# OmniRotor.net
KiCad netlist of a schematic drawn in EAGLE
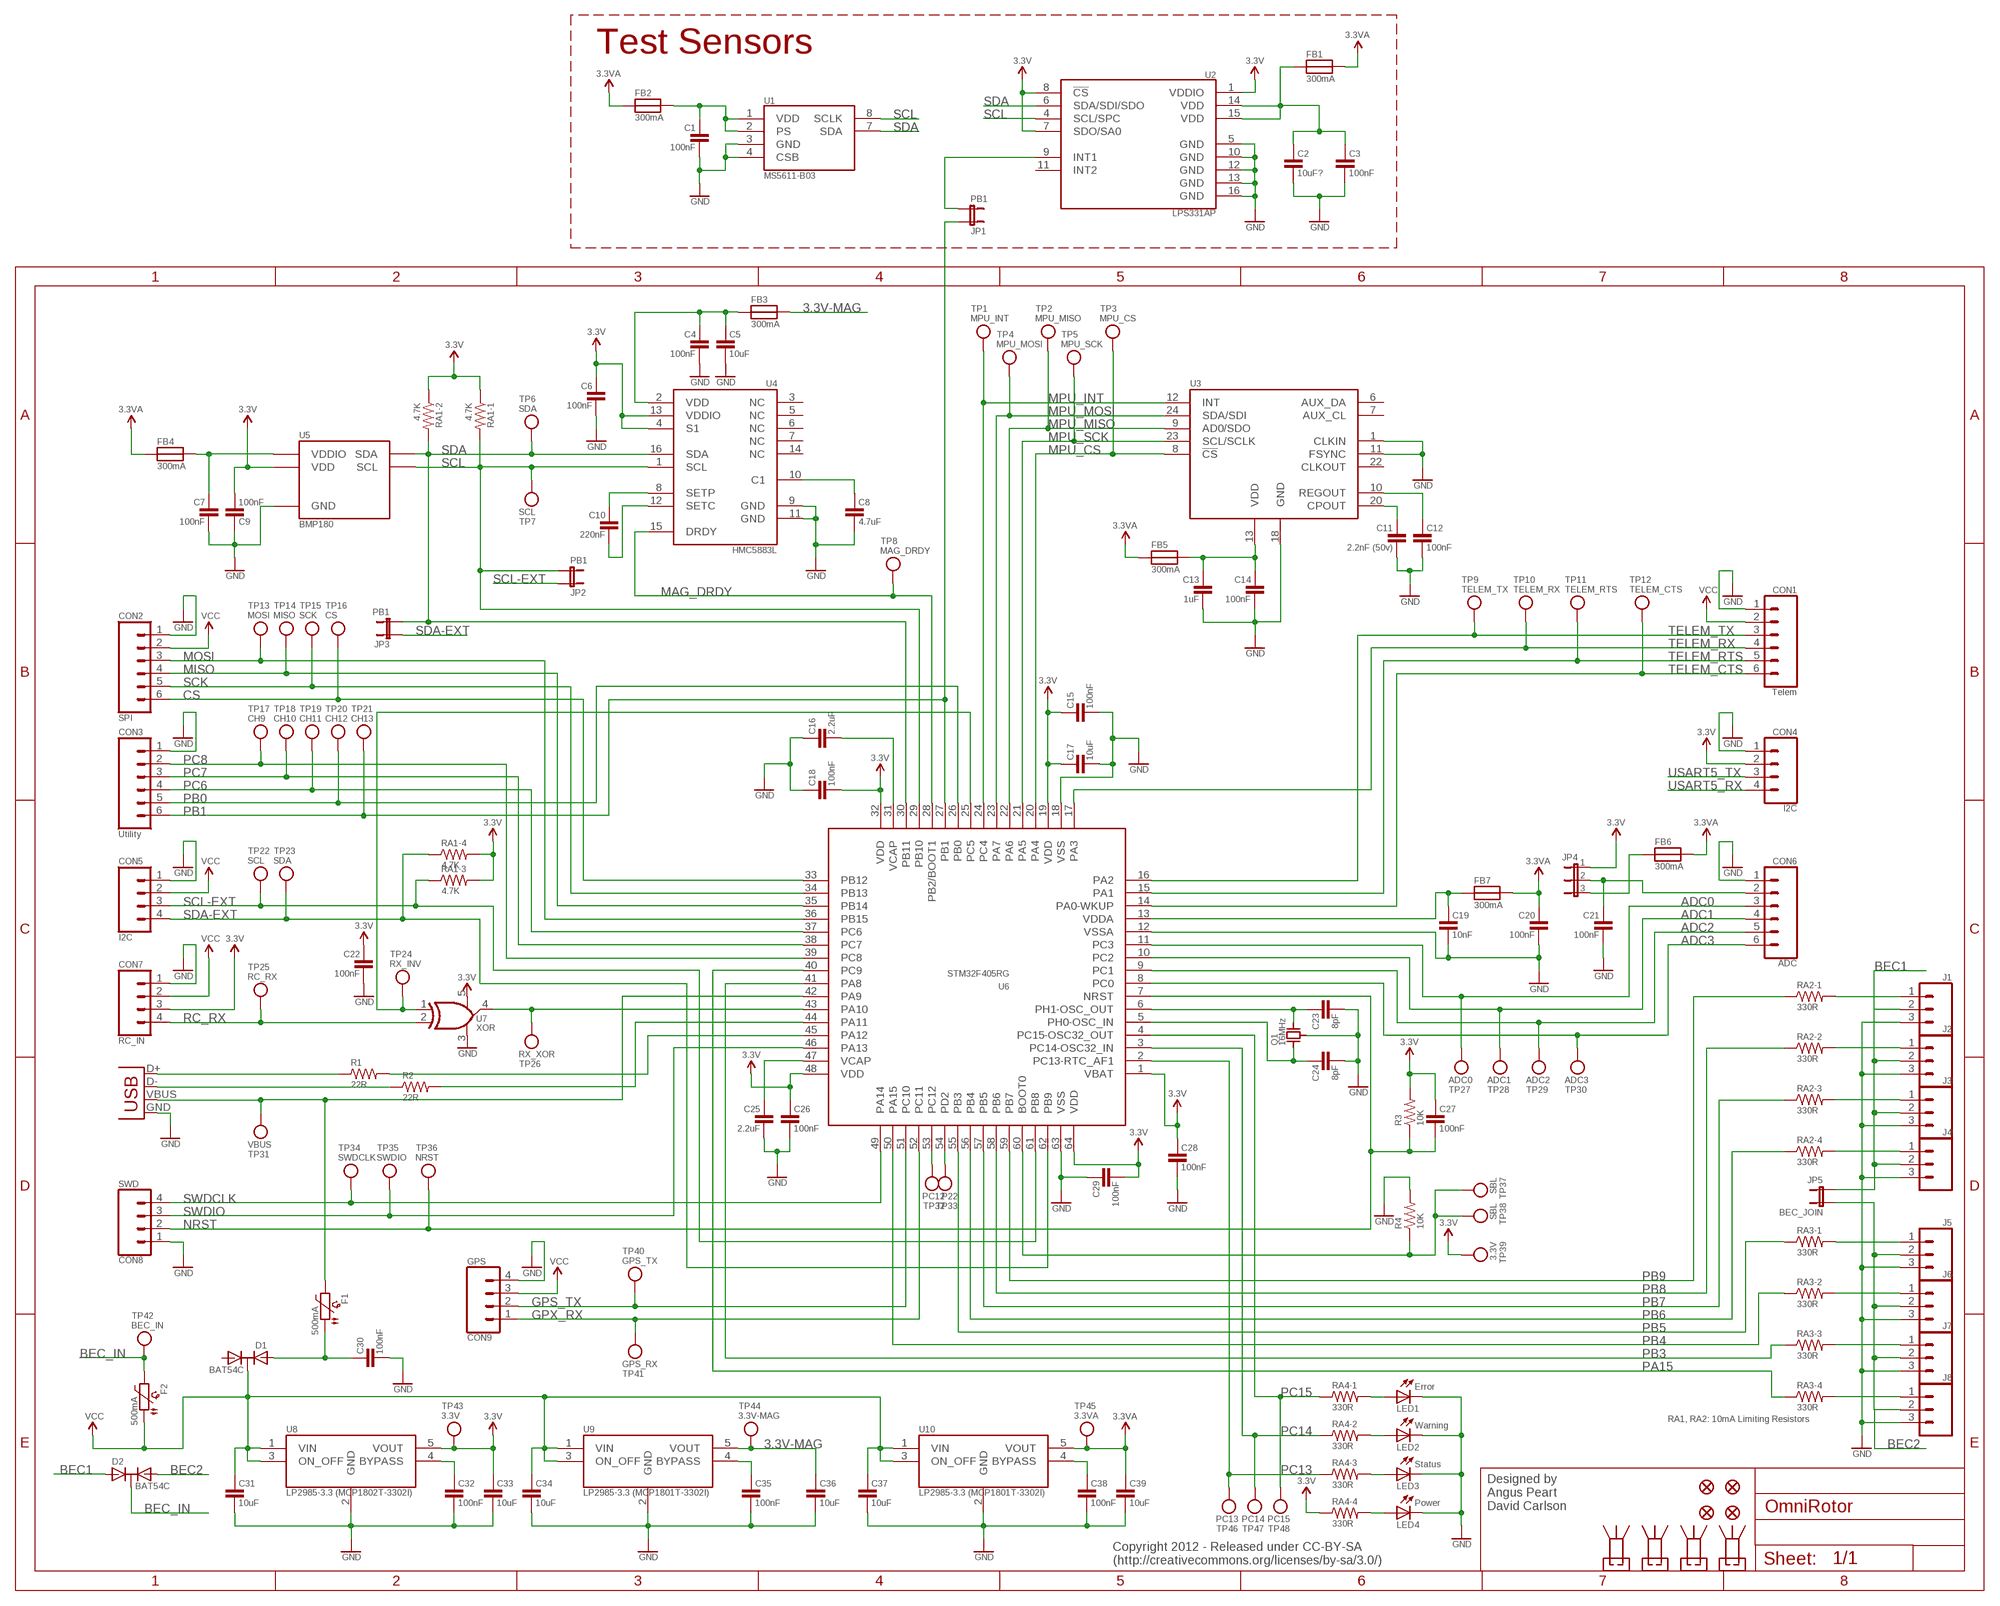
[diagram p0: schematic, sheet 1]

(export (version "E")
  (design (tool "Eeschema 10.0.6"))
  (components
    (comp (ref "C1")
      (value "100nF")
      (footprint "eagle-import:0402-CAP@1")
      (libsource (lib "eagle-import") (part "CAPACITOR0402"))
    )
    (comp (ref "C2")
      (value "10uF?")
      (footprint "eagle-import:0603@1")
      (libsource (lib "eagle-import") (part "CAPACITOR0603"))
    )
    (comp (ref "C3")
      (value "100nF")
      (footprint "eagle-import:0402-CAP@1")
      (libsource (lib "eagle-import") (part "CAPACITOR0402"))
    )
    (comp (ref "C4")
      (value "100nF")
      (footprint "eagle-import:0402-CAP@1")
      (libsource (lib "eagle-import") (part "CAPACITOR0402"))
    )
    (comp (ref "C5")
      (value "10uF")
      (footprint "eagle-import:0805@1")
      (libsource (lib "eagle-import") (part "CAPACITOR0805"))
    )
    (comp (ref "C6")
      (value "100nF")
      (footprint "eagle-import:0402-CAP@1")
      (libsource (lib "eagle-import") (part "CAPACITOR0402"))
    )
    (comp (ref "C7")
      (value "100nF")
      (footprint "eagle-import:0402-CAP@1")
      (libsource (lib "eagle-import") (part "CAPACITOR0402"))
    )
    (comp (ref "C8")
      (value "4.7uF")
      (footprint "eagle-import:0603@1")
      (libsource (lib "eagle-import") (part "CAPACITOR0603"))
    )
    (comp (ref "C9")
      (value "100nF")
      (footprint "eagle-import:0402-CAP@1")
      (libsource (lib "eagle-import") (part "CAPACITOR0402"))
    )
    (comp (ref "C10")
      (value "220nF")
      (footprint "eagle-import:0402-CAP@1")
      (libsource (lib "eagle-import") (part "CAPACITOR0402"))
    )
    (comp (ref "C11")
      (value "2.2nF (50v)")
      (footprint "eagle-import:0402-CAP@1")
      (libsource (lib "eagle-import") (part "CAPACITOR0402"))
    )
    (comp (ref "C12")
      (value "100nF")
      (footprint "eagle-import:0402-CAP@1")
      (libsource (lib "eagle-import") (part "CAPACITOR0402"))
    )
    (comp (ref "C13")
      (value "1uF")
      (footprint "eagle-import:0603@1")
      (libsource (lib "eagle-import") (part "CAPACITOR0603"))
    )
    (comp (ref "C14")
      (value "100nF")
      (footprint "eagle-import:0402-CAP@1")
      (libsource (lib "eagle-import") (part "CAPACITOR0402"))
    )
    (comp (ref "C15")
      (value "100nF")
      (footprint "eagle-import:0402-CAP@1")
      (libsource (lib "eagle-import") (part "CAPACITOR0402"))
    )
    (comp (ref "C16")
      (value "2.2uF")
      (footprint "eagle-import:0603@1")
      (libsource (lib "eagle-import") (part "CAPACITOR0603"))
    )
    (comp (ref "C17")
      (value "10uF")
      (footprint "eagle-import:0805")
      (libsource (lib "eagle-import") (part "CAPACITOR-CERAMIC0805"))
    )
    (comp (ref "C18")
      (value "100nF")
      (footprint "eagle-import:0402-CAP@1")
      (libsource (lib "eagle-import") (part "CAPACITOR0402"))
    )
    (comp (ref "C19")
      (value "10nF")
      (footprint "eagle-import:0402-CAP@1")
      (libsource (lib "eagle-import") (part "CAPACITOR0402"))
    )
    (comp (ref "C20")
      (value "100nF")
      (footprint "eagle-import:0402-CAP@1")
      (libsource (lib "eagle-import") (part "CAPACITOR0402"))
    )
    (comp (ref "C21")
      (value "100nF")
      (footprint "eagle-import:0402-CAP@1")
      (libsource (lib "eagle-import") (part "CAPACITOR0402"))
    )
    (comp (ref "C22")
      (value "100nF")
      (footprint "eagle-import:0402-CAP@1")
      (libsource (lib "eagle-import") (part "CAPACITOR0402"))
    )
    (comp (ref "C23")
      (value "8pF")
      (footprint "eagle-import:0402-CAP@1")
      (libsource (lib "eagle-import") (part "CAPACITOR0402"))
    )
    (comp (ref "C24")
      (value "8pF")
      (footprint "eagle-import:0402-CAP@1")
      (libsource (lib "eagle-import") (part "CAPACITOR0402"))
    )
    (comp (ref "C25")
      (value "2.2uF")
      (footprint "eagle-import:0603@1")
      (libsource (lib "eagle-import") (part "CAPACITOR0603"))
    )
    (comp (ref "C26")
      (value "100nF")
      (footprint "eagle-import:0402-CAP@1")
      (libsource (lib "eagle-import") (part "CAPACITOR0402"))
    )
    (comp (ref "C27")
      (value "100nF")
      (footprint "eagle-import:0402-CAP@1")
      (libsource (lib "eagle-import") (part "CAPACITOR0402"))
    )
    (comp (ref "C28")
      (value "100nF")
      (footprint "eagle-import:0402-CAP@1")
      (libsource (lib "eagle-import") (part "CAPACITOR0402"))
    )
    (comp (ref "C29")
      (value "100nF")
      (footprint "eagle-import:0402-CAP@1")
      (libsource (lib "eagle-import") (part "CAPACITOR0402"))
    )
    (comp (ref "C30")
      (value "100nF")
      (footprint "eagle-import:0402-CAP@1")
      (libsource (lib "eagle-import") (part "CAPACITOR0402"))
    )
    (comp (ref "C31")
      (value "10uF")
      (footprint "eagle-import:0805")
      (libsource (lib "eagle-import") (part "CAPACITOR-CERAMIC0805"))
    )
    (comp (ref "C32")
      (value "100nF")
      (footprint "eagle-import:0402-CAP@1")
      (libsource (lib "eagle-import") (part "CAPACITOR0402"))
    )
    (comp (ref "C33")
      (value "10uF")
      (footprint "eagle-import:0805")
      (libsource (lib "eagle-import") (part "CAPACITOR-CERAMIC0805"))
    )
    (comp (ref "C34")
      (value "10uF")
      (footprint "eagle-import:0805")
      (libsource (lib "eagle-import") (part "CAPACITOR-CERAMIC0805"))
    )
    (comp (ref "C35")
      (value "100nF")
      (footprint "eagle-import:0402-CAP@1")
      (libsource (lib "eagle-import") (part "CAPACITOR0402"))
    )
    (comp (ref "C36")
      (value "10uF")
      (footprint "eagle-import:0805")
      (libsource (lib "eagle-import") (part "CAPACITOR-CERAMIC0805"))
    )
    (comp (ref "C37")
      (value "10uF")
      (footprint "eagle-import:0805")
      (libsource (lib "eagle-import") (part "CAPACITOR-CERAMIC0805"))
    )
    (comp (ref "C38")
      (value "100nF")
      (footprint "eagle-import:0402-CAP@1")
      (libsource (lib "eagle-import") (part "CAPACITOR0402"))
    )
    (comp (ref "C39")
      (value "10uF")
      (footprint "eagle-import:0805")
      (libsource (lib "eagle-import") (part "CAPACITOR-CERAMIC0805"))
    )
    (comp (ref "CON1")
      (value "Telem")
      (footprint "eagle-import:SM06B-SRSS-TB")
      (libsource (lib "eagle-import") (part "M06JST-SH-SIDE"))
    )
    (comp (ref "CON2")
      (value "SPI")
      (footprint "eagle-import:SM06B-SRSS-TB")
      (libsource (lib "eagle-import") (part "M06JST-SH-SIDE"))
    )
    (comp (ref "CON3")
      (value "Utility")
      (footprint "eagle-import:SM06B-SRSS-TB")
      (libsource (lib "eagle-import") (part "M06JST-SH-SIDE"))
    )
    (comp (ref "CON4")
      (value "I2C")
      (footprint "eagle-import:SM04B-SRSS-TB")
      (libsource (lib "eagle-import") (part "M04JST-SH-SIDE"))
    )
    (comp (ref "CON5")
      (value "I2C")
      (footprint "eagle-import:SM04B-SRSS-TB")
      (libsource (lib "eagle-import") (part "M04JST-SH-SIDE"))
    )
    (comp (ref "CON6")
      (value "ADC")
      (footprint "eagle-import:SM06B-SRSS-TB")
      (libsource (lib "eagle-import") (part "M06JST-SH-SIDE"))
    )
    (comp (ref "CON7")
      (value "RC_IN")
      (footprint "eagle-import:SM04B-SRSS-TB")
      (libsource (lib "eagle-import") (part "M04JST-SH-SIDE"))
    )
    (comp (ref "CON8")
      (value "SWD")
      (footprint "eagle-import:BM04B-SRSS-TB")
      (libsource (lib "eagle-import") (part "M04JST-SH-TOP"))
    )
    (comp (ref "CON9")
      (value "GPS")
      (footprint "eagle-import:SM04B-SRSS-TB")
      (libsource (lib "eagle-import") (part "M04JST-SH-SIDE"))
    )
    (comp (ref "D1")
      (value "BAT54C")
      (footprint "eagle-import:SOT23")
      (libsource (lib "eagle-import") (part "BAT54C"))
    )
    (comp (ref "D2")
      (value "BAT54C")
      (footprint "eagle-import:SOT23")
      (libsource (lib "eagle-import") (part "BAT54C"))
    )
    (comp (ref "F1")
      (value "500mA")
      (footprint "eagle-import:1210-PTC")
      (libsource (lib "eagle-import") (part "PTC1210"))
    )
    (comp (ref "F2")
      (value "500mA")
      (footprint "eagle-import:1210-PTC")
      (libsource (lib "eagle-import") (part "PTC1210"))
    )
    (comp (ref "FB1")
      (value "300mA")
      (footprint "eagle-import:0603")
      (libsource (lib "eagle-import") (part "FERRITE0603"))
    )
    (comp (ref "FB2")
      (value "300mA")
      (footprint "eagle-import:0603")
      (libsource (lib "eagle-import") (part "FERRITE0603"))
    )
    (comp (ref "FB3")
      (value "300mA")
      (footprint "eagle-import:0603")
      (libsource (lib "eagle-import") (part "FERRITE0603"))
    )
    (comp (ref "FB4")
      (value "300mA")
      (footprint "eagle-import:0603")
      (libsource (lib "eagle-import") (part "FERRITE0603"))
    )
    (comp (ref "FB5")
      (value "300mA")
      (footprint "eagle-import:0603")
      (libsource (lib "eagle-import") (part "FERRITE0603"))
    )
    (comp (ref "FB6")
      (value "300mA")
      (footprint "eagle-import:0603")
      (libsource (lib "eagle-import") (part "FERRITE0603"))
    )
    (comp (ref "FB7")
      (value "300mA")
      (footprint "eagle-import:0603")
      (libsource (lib "eagle-import") (part "FERRITE0603"))
    )
    (comp (ref "FID1")
      (value "FIDUCIAL1X2.5")
      (footprint "eagle-import:FIDUCIAL-1X2.5")
      (libsource (lib "eagle-import") (part "FIDUCIAL1X2.5"))
    )
    (comp (ref "FID2")
      (value "FIDUCIAL1X2.5")
      (footprint "eagle-import:FIDUCIAL-1X2.5")
      (libsource (lib "eagle-import") (part "FIDUCIAL1X2.5"))
    )
    (comp (ref "FID3")
      (value "FIDUCIAL1X2.5")
      (footprint "eagle-import:FIDUCIAL-1X2.5")
      (libsource (lib "eagle-import") (part "FIDUCIAL1X2.5"))
    )
    (comp (ref "FID4")
      (value "FIDUCIAL1X2.5")
      (footprint "eagle-import:FIDUCIAL-1X2.5")
      (libsource (lib "eagle-import") (part "FIDUCIAL1X2.5"))
    )
    (comp (ref "J1")
      (value "M03PTH")
      (footprint "eagle-import:1X03")
      (libsource (lib "eagle-import") (part "M03PTH"))
    )
    (comp (ref "J2")
      (value "M03PTH")
      (footprint "eagle-import:1X03")
      (libsource (lib "eagle-import") (part "M03PTH"))
    )
    (comp (ref "J3")
      (value "M03PTH")
      (footprint "eagle-import:1X03")
      (libsource (lib "eagle-import") (part "M03PTH"))
    )
    (comp (ref "J4")
      (value "M03PTH")
      (footprint "eagle-import:1X03")
      (libsource (lib "eagle-import") (part "M03PTH"))
    )
    (comp (ref "J5")
      (value "M03PTH")
      (footprint "eagle-import:1X03")
      (libsource (lib "eagle-import") (part "M03PTH"))
    )
    (comp (ref "J6")
      (value "M03PTH")
      (footprint "eagle-import:1X03")
      (libsource (lib "eagle-import") (part "M03PTH"))
    )
    (comp (ref "J7")
      (value "M03PTH")
      (footprint "eagle-import:1X03")
      (libsource (lib "eagle-import") (part "M03PTH"))
    )
    (comp (ref "J8")
      (value "M03PTH")
      (footprint "eagle-import:1X03")
      (libsource (lib "eagle-import") (part "M03PTH"))
    )
    (comp (ref "JP1")
      (value "PB1")
      (footprint "eagle-import:SJ_2_NO")
      (libsource (lib "eagle-import") (part "JUMPER-2NO"))
    )
    (comp (ref "JP2")
      (value "PB1")
      (footprint "eagle-import:SJ_2_NO")
      (libsource (lib "eagle-import") (part "JUMPER-2NO"))
    )
    (comp (ref "JP3")
      (value "PB1")
      (footprint "eagle-import:SJ_2_NO")
      (libsource (lib "eagle-import") (part "JUMPER-2NO"))
    )
    (comp (ref "JP4")
      (value "JUMPER-31-2")
      (footprint "eagle-import:SJ_3_PASTE1&2")
      (libsource (lib "eagle-import") (part "JUMPER-31-2"))
    )
    (comp (ref "JP5")
      (value "BEC_JOIN")
      (footprint "eagle-import:SJ_2_NO")
      (libsource (lib "eagle-import") (part "JUMPER-2NO"))
    )
    (comp (ref "LED1")
      (value "Error")
      (footprint "eagle-import:0603_LED")
      (libsource (lib "eagle-import") (part "LED0603"))
    )
    (comp (ref "LED2")
      (value "Warning")
      (footprint "eagle-import:0603_LED")
      (libsource (lib "eagle-import") (part "LED0603"))
    )
    (comp (ref "LED3")
      (value "Status")
      (footprint "eagle-import:0603_LED")
      (libsource (lib "eagle-import") (part "LED0603"))
    )
    (comp (ref "LED4")
      (value "Power")
      (footprint "eagle-import:0603_LED")
      (libsource (lib "eagle-import") (part "LED0603"))
    )
    (comp (ref "LP1")
      (value "LIGHTPIPE")
      (footprint "eagle-import:VLP-LIGHTPIPES")
      (libsource (lib "eagle-import") (part "LIGHTPIPE"))
    )
    (comp (ref "LP2")
      (value "LIGHTPIPE")
      (footprint "eagle-import:VLP-LIGHTPIPES")
      (libsource (lib "eagle-import") (part "LIGHTPIPE"))
    )
    (comp (ref "LP3")
      (value "LIGHTPIPE")
      (footprint "eagle-import:VLP-LIGHTPIPES")
      (libsource (lib "eagle-import") (part "LIGHTPIPE"))
    )
    (comp (ref "LP4")
      (value "LIGHTPIPE")
      (footprint "eagle-import:VLP-LIGHTPIPES")
      (libsource (lib "eagle-import") (part "LIGHTPIPE"))
    )
    (comp (ref "Q1")
      (value "16MHz")
      (footprint "eagle-import:CRYSTAL_3-2X2-5")
      (libsource (lib "eagle-import") (part "CRYSTAL-GND"))
    )
    (comp (ref "R1")
      (value "22R")
      (footprint "eagle-import:0402-RES")
      (libsource (lib "eagle-import") (part "RESISTOR0402"))
    )
    (comp (ref "R2")
      (value "22R")
      (footprint "eagle-import:0402-RES")
      (libsource (lib "eagle-import") (part "RESISTOR0402"))
    )
    (comp (ref "R3")
      (value "10K")
      (footprint "eagle-import:0402-RES")
      (libsource (lib "eagle-import") (part "RESISTOR0402"))
    )
    (comp (ref "R4")
      (value "10K")
      (footprint "eagle-import:0402-RES")
      (libsource (lib "eagle-import") (part "RESISTOR0402"))
    )
    (comp (ref "RA1")
      (value "4.7K")
      (footprint "eagle-import:1206-ARRAY")
      (libsource (lib "eagle-import") (part "RESISTOR-ARRAY-1206"))
    )
    (comp (ref "RA2")
      (value "330R")
      (footprint "eagle-import:1206-ARRAY")
      (libsource (lib "eagle-import") (part "RESISTOR-ARRAY-1206"))
    )
    (comp (ref "RA3")
      (value "330R")
      (footprint "eagle-import:1206-ARRAY")
      (libsource (lib "eagle-import") (part "RESISTOR-ARRAY-1206"))
    )
    (comp (ref "RA4")
      (value "330R")
      (footprint "eagle-import:1206-ARRAY")
      (libsource (lib "eagle-import") (part "RESISTOR-ARRAY-1206"))
    )
    (comp (ref "TP1")
      (value "MPU_INT")
      (footprint "eagle-import:TESTPOINT_ROUND_0.7MM")
      (libsource (lib "eagle-import") (part "TESTPOINTROUND0.7MM"))
    )
    (comp (ref "TP2")
      (value "MPU_MISO")
      (footprint "eagle-import:TESTPOINT_ROUND_0.7MM")
      (libsource (lib "eagle-import") (part "TESTPOINTROUND0.7MM"))
    )
    (comp (ref "TP3")
      (value "MPU_CS")
      (footprint "eagle-import:TESTPOINT_ROUND_0.7MM")
      (libsource (lib "eagle-import") (part "TESTPOINTROUND0.7MM"))
    )
    (comp (ref "TP4")
      (value "MPU_MOSI")
      (footprint "eagle-import:TESTPOINT_ROUND_0.7MM")
      (libsource (lib "eagle-import") (part "TESTPOINTROUND0.7MM"))
    )
    (comp (ref "TP5")
      (value "MPU_SCK")
      (footprint "eagle-import:TESTPOINT_ROUND_0.7MM")
      (libsource (lib "eagle-import") (part "TESTPOINTROUND0.7MM"))
    )
    (comp (ref "TP6")
      (value "SDA")
      (footprint "eagle-import:TESTPOINT_ROUND_0.7MM")
      (libsource (lib "eagle-import") (part "TESTPOINTROUND0.7MM"))
    )
    (comp (ref "TP7")
      (value "SCL")
      (footprint "eagle-import:TESTPOINT_ROUND_0.7MM")
      (libsource (lib "eagle-import") (part "TESTPOINTROUND0.7MM"))
    )
    (comp (ref "TP8")
      (value "MAG_DRDY")
      (footprint "eagle-import:TESTPOINT_ROUND_0.7MM")
      (libsource (lib "eagle-import") (part "TESTPOINTROUND0.7MM"))
    )
    (comp (ref "TP9")
      (value "TELEM_TX")
      (footprint "eagle-import:TESTPOINT_ROUND_0.7MM")
      (libsource (lib "eagle-import") (part "TESTPOINTROUND0.7MM"))
    )
    (comp (ref "TP10")
      (value "TELEM_RX")
      (footprint "eagle-import:TESTPOINT_ROUND_0.7MM")
      (libsource (lib "eagle-import") (part "TESTPOINTROUND0.7MM"))
    )
    (comp (ref "TP11")
      (value "TELEM_RTS")
      (footprint "eagle-import:TESTPOINT_ROUND_0.7MM")
      (libsource (lib "eagle-import") (part "TESTPOINTROUND0.7MM"))
    )
    (comp (ref "TP12")
      (value "TELEM_CTS")
      (footprint "eagle-import:TESTPOINT_ROUND_0.7MM")
      (libsource (lib "eagle-import") (part "TESTPOINTROUND0.7MM"))
    )
    (comp (ref "TP13")
      (value "MOSI")
      (footprint "eagle-import:TESTPOINT_ROUND_0.7MM")
      (libsource (lib "eagle-import") (part "TESTPOINTROUND0.7MM"))
    )
    (comp (ref "TP14")
      (value "MISO")
      (footprint "eagle-import:TESTPOINT_ROUND_0.7MM")
      (libsource (lib "eagle-import") (part "TESTPOINTROUND0.7MM"))
    )
    (comp (ref "TP15")
      (value "SCK")
      (footprint "eagle-import:TESTPOINT_ROUND_0.7MM")
      (libsource (lib "eagle-import") (part "TESTPOINTROUND0.7MM"))
    )
    (comp (ref "TP16")
      (value "CS")
      (footprint "eagle-import:TESTPOINT_ROUND_0.7MM")
      (libsource (lib "eagle-import") (part "TESTPOINTROUND0.7MM"))
    )
    (comp (ref "TP17")
      (value "CH9")
      (footprint "eagle-import:TESTPOINT_ROUND_0.7MM")
      (libsource (lib "eagle-import") (part "TESTPOINTROUND0.7MM"))
    )
    (comp (ref "TP18")
      (value "CH10")
      (footprint "eagle-import:TESTPOINT_ROUND_0.7MM")
      (libsource (lib "eagle-import") (part "TESTPOINTROUND0.7MM"))
    )
    (comp (ref "TP19")
      (value "CH11")
      (footprint "eagle-import:TESTPOINT_ROUND_0.7MM")
      (libsource (lib "eagle-import") (part "TESTPOINTROUND0.7MM"))
    )
    (comp (ref "TP20")
      (value "CH12")
      (footprint "eagle-import:TESTPOINT_ROUND_0.7MM")
      (libsource (lib "eagle-import") (part "TESTPOINTROUND0.7MM"))
    )
    (comp (ref "TP21")
      (value "CH13")
      (footprint "eagle-import:TESTPOINT_ROUND_0.7MM")
      (libsource (lib "eagle-import") (part "TESTPOINTROUND0.7MM"))
    )
    (comp (ref "TP22")
      (value "SCL")
      (footprint "eagle-import:TESTPOINT_ROUND_0.7MM")
      (libsource (lib "eagle-import") (part "TESTPOINTROUND0.7MM"))
    )
    (comp (ref "TP23")
      (value "SDA")
      (footprint "eagle-import:TESTPOINT_ROUND_0.7MM")
      (libsource (lib "eagle-import") (part "TESTPOINTROUND0.7MM"))
    )
    (comp (ref "TP24")
      (value "RX_INV")
      (footprint "eagle-import:TESTPOINT_ROUND_0.7MM")
      (libsource (lib "eagle-import") (part "TESTPOINTROUND0.7MM"))
    )
    (comp (ref "TP25")
      (value "RC_RX")
      (footprint "eagle-import:TESTPOINT_ROUND_0.7MM")
      (libsource (lib "eagle-import") (part "TESTPOINTROUND0.7MM"))
    )
    (comp (ref "TP26")
      (value "RX_XOR")
      (footprint "eagle-import:TESTPOINT_ROUND_0.7MM")
      (libsource (lib "eagle-import") (part "TESTPOINTROUND0.7MM"))
    )
    (comp (ref "TP27")
      (value "ADC0")
      (footprint "eagle-import:TESTPOINT_ROUND_0.7MM")
      (libsource (lib "eagle-import") (part "TESTPOINTROUND0.7MM"))
    )
    (comp (ref "TP28")
      (value "ADC1")
      (footprint "eagle-import:TESTPOINT_ROUND_0.7MM")
      (libsource (lib "eagle-import") (part "TESTPOINTROUND0.7MM"))
    )
    (comp (ref "TP29")
      (value "ADC2")
      (footprint "eagle-import:TESTPOINT_ROUND_0.7MM")
      (libsource (lib "eagle-import") (part "TESTPOINTROUND0.7MM"))
    )
    (comp (ref "TP30")
      (value "ADC3")
      (footprint "eagle-import:TESTPOINT_ROUND_0.7MM")
      (libsource (lib "eagle-import") (part "TESTPOINTROUND0.7MM"))
    )
    (comp (ref "TP31")
      (value "VBUS")
      (footprint "eagle-import:TESTPOINT_ROUND_0.7MM")
      (libsource (lib "eagle-import") (part "TESTPOINTROUND0.7MM"))
    )
    (comp (ref "TP32")
      (value "PC12")
      (footprint "eagle-import:TESTPOINT_ROUND_0.7MM")
      (libsource (lib "eagle-import") (part "TESTPOINTROUND0.7MM"))
    )
    (comp (ref "TP33")
      (value "P22")
      (footprint "eagle-import:TESTPOINT_ROUND_0.7MM")
      (libsource (lib "eagle-import") (part "TESTPOINTROUND0.7MM"))
    )
    (comp (ref "TP34")
      (value "SWDCLK")
      (footprint "eagle-import:TESTPOINT_ROUND_0.7MM")
      (libsource (lib "eagle-import") (part "TESTPOINTROUND0.7MM"))
    )
    (comp (ref "TP35")
      (value "SWDIO")
      (footprint "eagle-import:TESTPOINT_ROUND_0.7MM")
      (libsource (lib "eagle-import") (part "TESTPOINTROUND0.7MM"))
    )
    (comp (ref "TP36")
      (value "NRST")
      (footprint "eagle-import:TESTPOINT_ROUND_0.7MM")
      (libsource (lib "eagle-import") (part "TESTPOINTROUND0.7MM"))
    )
    (comp (ref "TP37")
      (value "SBL")
      (footprint "eagle-import:TESTPOINT_ROUND_1MM")
      (libsource (lib "eagle-import") (part "TESTPOINTROUND1MM"))
    )
    (comp (ref "TP38")
      (value "SBL")
      (footprint "eagle-import:TESTPOINT_ROUND_1.5MM")
      (libsource (lib "eagle-import") (part "TESTPOINTROUND1.5MM"))
    )
    (comp (ref "TP39")
      (value "3.3V")
      (footprint "eagle-import:TESTPOINT_ROUND_1.5MM")
      (libsource (lib "eagle-import") (part "TESTPOINTROUND1.5MM"))
    )
    (comp (ref "TP40")
      (value "GPS_TX")
      (footprint "eagle-import:TESTPOINT_ROUND_0.7MM")
      (libsource (lib "eagle-import") (part "TESTPOINTROUND0.7MM"))
    )
    (comp (ref "TP41")
      (value "GPS_RX")
      (footprint "eagle-import:TESTPOINT_ROUND_0.7MM")
      (libsource (lib "eagle-import") (part "TESTPOINTROUND0.7MM"))
    )
    (comp (ref "TP42")
      (value "BEC_IN")
      (footprint "eagle-import:TESTPOINT_ROUND_0.7MM")
      (libsource (lib "eagle-import") (part "TESTPOINTROUND0.7MM"))
    )
    (comp (ref "TP43")
      (value "3.3V")
      (footprint "eagle-import:TESTPOINT_ROUND_0.7MM")
      (libsource (lib "eagle-import") (part "TESTPOINTROUND0.7MM"))
    )
    (comp (ref "TP44")
      (value "3.3V-MAG")
      (footprint "eagle-import:TESTPOINT_ROUND_0.7MM")
      (libsource (lib "eagle-import") (part "TESTPOINTROUND0.7MM"))
    )
    (comp (ref "TP45")
      (value "3.3VA")
      (footprint "eagle-import:TESTPOINT_ROUND_0.7MM")
      (libsource (lib "eagle-import") (part "TESTPOINTROUND0.7MM"))
    )
    (comp (ref "TP46")
      (value "PC13")
      (footprint "eagle-import:TESTPOINT_ROUND_0.7MM")
      (libsource (lib "eagle-import") (part "TESTPOINTROUND0.7MM"))
    )
    (comp (ref "TP47")
      (value "PC14")
      (footprint "eagle-import:TESTPOINT_ROUND_0.7MM")
      (libsource (lib "eagle-import") (part "TESTPOINTROUND0.7MM"))
    )
    (comp (ref "TP48")
      (value "PC15")
      (footprint "eagle-import:TESTPOINT_ROUND_0.7MM")
      (libsource (lib "eagle-import") (part "TESTPOINTROUND0.7MM"))
    )
    (comp (ref "U1")
      (value "MS5611-B03")
      (footprint "eagle-import:MS5611")
      (libsource (lib "eagle-import") (part "MS5611"))
    )
    (comp (ref "U2")
      (value "LPS331AP")
      (footprint "eagle-import:HCLGA-16L")
      (libsource (lib "eagle-import") (part "LPS331AP"))
    )
    (comp (ref "U3")
      (value "MPU6000")
      (footprint "eagle-import:QFN-24")
      (libsource (lib "eagle-import") (part "MPU6000"))
    )
    (comp (ref "U4")
      (value "HMC5883L")
      (footprint "eagle-import:16LPCC")
      (libsource (lib "eagle-import") (part "HMC5883L"))
    )
    (comp (ref "U5")
      (value "BMP180")
      (footprint "eagle-import:BMP180")
      (libsource (lib "eagle-import") (part "BMP180"))
    )
    (comp (ref "U6")
      (value "STM32F405RG")
      (footprint "eagle-import:LQFP64")
      (libsource (lib "eagle-import") (part "STM32FX05R"))
    )
    (comp (ref "U7")
      (value "XOR")
      (footprint "eagle-import:SC-70-5")
      (libsource (lib "eagle-import") (part "74LVC1G86SC70"))
    )
    (comp (ref "U8")
      (value "LP2985-3.3 (MCP1802T-3302I)")
      (footprint "eagle-import:SOT-23-5")
      (libsource (lib "eagle-import") (part "LP2985"))
    )
    (comp (ref "U9")
      (value "LP2985-3.3 (MCP1801T-3302I)")
      (footprint "eagle-import:SOT-23-5")
      (libsource (lib "eagle-import") (part "LP2985"))
    )
    (comp (ref "U10")
      (value "LP2985-3.3 (MCP1801T-3302I)")
      (footprint "eagle-import:SOT-23-5")
      (libsource (lib "eagle-import") (part "LP2985"))
    )
    (comp (ref "USB1")
      (value "USB-MICRO-B")
      (footprint "eagle-import:USB-MICRO-B")
      (libsource (lib "eagle-import") (part "USBMICRO-B"))
    )
  )
  (nets
    (net (code "1") (name "/3.3V-MAG") (class "Default")
      (node (ref "C36") (pin "1") (pinfunction "1_1") (pintype "passive"))
      (node (ref "FB3") (pin "2") (pinfunction "2_2") (pintype "passive"))
      (node (ref "TP44") (pin "1") (pinfunction "1_1") (pintype "bidirectional"))
      (node (ref "U9") (pin "5") (pinfunction "VOUT_5") (pintype "passive"))
    )
    (net (code "2") (name "/ADC0") (class "Default")
      (node (ref "CON6") (pin "3") (pinfunction "3_3") (pintype "passive"))
      (node (ref "TP27") (pin "1") (pinfunction "1_1") (pintype "bidirectional"))
      (node (ref "U6") (pin "11") (pinfunction "PC3_11") (pintype "bidirectional"))
    )
    (net (code "3") (name "/ADC1") (class "Default")
      (node (ref "CON6") (pin "4") (pinfunction "4_4") (pintype "passive"))
      (node (ref "TP28") (pin "1") (pinfunction "1_1") (pintype "bidirectional"))
      (node (ref "U6") (pin "10") (pinfunction "PC2_10") (pintype "bidirectional"))
    )
    (net (code "4") (name "/ADC2") (class "Default")
      (node (ref "CON6") (pin "5") (pinfunction "5_5") (pintype "passive"))
      (node (ref "TP29") (pin "1") (pinfunction "1_1") (pintype "bidirectional"))
      (node (ref "U6") (pin "9") (pinfunction "PC1_9") (pintype "bidirectional"))
    )
    (net (code "5") (name "/ADC3") (class "Default")
      (node (ref "CON6") (pin "6") (pinfunction "6_6") (pintype "passive"))
      (node (ref "TP30") (pin "1") (pinfunction "1_1") (pintype "bidirectional"))
      (node (ref "U6") (pin "8") (pinfunction "PC0_8") (pintype "bidirectional"))
    )
    (net (code "6") (name "/BEC1") (class "Default")
      (node (ref "D2") (pin "1") (pinfunction "P$1_1") (pintype "input"))
      (node (ref "J1") (pin "2") (pinfunction "2_2") (pintype "passive"))
      (node (ref "J2") (pin "2") (pinfunction "2_2") (pintype "passive"))
      (node (ref "J3") (pin "2") (pinfunction "2_2") (pintype "passive"))
      (node (ref "J4") (pin "2") (pinfunction "2_2") (pintype "passive"))
      (node (ref "JP5") (pin "1") (pinfunction "1_1") (pintype "passive"))
    )
    (net (code "7") (name "/BEC2") (class "Default")
      (node (ref "D2") (pin "2") (pinfunction "P$2_2") (pintype "input"))
      (node (ref "J5") (pin "2") (pinfunction "2_2") (pintype "passive"))
      (node (ref "J6") (pin "2") (pinfunction "2_2") (pintype "passive"))
      (node (ref "J7") (pin "2") (pinfunction "2_2") (pintype "passive"))
      (node (ref "J8") (pin "2") (pinfunction "2_2") (pintype "passive"))
      (node (ref "JP5") (pin "2") (pinfunction "2_2") (pintype "passive"))
    )
    (net (code "8") (name "/BEC_IN") (class "Default")
      (node (ref "D2") (pin "3") (pinfunction "P$3_3") (pintype "output"))
      (node (ref "F2") (pin "1") (pinfunction "1_1") (pintype "bidirectional"))
      (node (ref "TP42") (pin "1") (pinfunction "1_1") (pintype "bidirectional"))
    )
    (net (code "9") (name "/CS") (class "Default")
      (node (ref "CON2") (pin "6") (pinfunction "6_6") (pintype "passive"))
      (node (ref "TP16") (pin "1") (pinfunction "1_1") (pintype "bidirectional"))
      (node (ref "U6") (pin "33") (pinfunction "PB12_33") (pintype "bidirectional"))
    )
    (net (code "10") (name "/GPS_TX") (class "Default")
      (node (ref "CON9") (pin "2") (pinfunction "2_2") (pintype "passive"))
      (node (ref "TP40") (pin "1") (pinfunction "1_1") (pintype "bidirectional"))
      (node (ref "U6") (pin "51") (pinfunction "PC10_51") (pintype "bidirectional"))
    )
    (net (code "11") (name "/GPX_RX") (class "Default")
      (node (ref "CON9") (pin "1") (pinfunction "1_1") (pintype "passive"))
      (node (ref "TP41") (pin "1") (pinfunction "1_1") (pintype "bidirectional"))
      (node (ref "U6") (pin "52") (pinfunction "PC11_52") (pintype "bidirectional"))
    )
    (net (code "12") (name "/MAG_DRDY") (class "Default")
      (node (ref "TP8") (pin "1") (pinfunction "1_1") (pintype "bidirectional"))
      (node (ref "U4") (pin "15") (pinfunction "DRDY_15") (pintype "bidirectional"))
      (node (ref "U6") (pin "28") (pinfunction "PB2/BOOT1_28") (pintype "bidirectional"))
    )
    (net (code "13") (name "/MISO") (class "Default")
      (node (ref "CON2") (pin "4") (pinfunction "4_4") (pintype "passive"))
      (node (ref "TP14") (pin "1") (pinfunction "1_1") (pintype "bidirectional"))
      (node (ref "U6") (pin "35") (pinfunction "PB14_35") (pintype "bidirectional"))
    )
    (net (code "14") (name "/MOSI") (class "Default")
      (node (ref "CON2") (pin "3") (pinfunction "3_3") (pintype "passive"))
      (node (ref "TP13") (pin "1") (pinfunction "1_1") (pintype "bidirectional"))
      (node (ref "U6") (pin "36") (pinfunction "PB15_36") (pintype "bidirectional"))
    )
    (net (code "15") (name "/MPU_CS") (class "Default")
      (node (ref "TP3") (pin "1") (pinfunction "1_1") (pintype "bidirectional"))
      (node (ref "U3") (pin "8") (pinfunction "~{CS}_8") (pintype "bidirectional"))
      (node (ref "U6") (pin "20") (pinfunction "PA4_20") (pintype "bidirectional"))
    )
    (net (code "16") (name "/MPU_INT") (class "Default")
      (node (ref "TP1") (pin "1") (pinfunction "1_1") (pintype "bidirectional"))
      (node (ref "U3") (pin "12") (pinfunction "INT_12") (pintype "bidirectional"))
      (node (ref "U6") (pin "24") (pinfunction "PC4_24") (pintype "bidirectional"))
    )
    (net (code "17") (name "/MPU_MISO") (class "Default")
      (node (ref "TP2") (pin "1") (pinfunction "1_1") (pintype "bidirectional"))
      (node (ref "U3") (pin "9") (pinfunction "AD0/SDO_9") (pintype "bidirectional"))
      (node (ref "U6") (pin "22") (pinfunction "PA6_22") (pintype "bidirectional"))
    )
    (net (code "18") (name "/MPU_MOSI") (class "Default")
      (node (ref "TP4") (pin "1") (pinfunction "1_1") (pintype "bidirectional"))
      (node (ref "U3") (pin "24") (pinfunction "SDA/SDI_24") (pintype "bidirectional"))
      (node (ref "U6") (pin "23") (pinfunction "PA7_23") (pintype "bidirectional"))
    )
    (net (code "19") (name "/MPU_SCK") (class "Default")
      (node (ref "TP5") (pin "1") (pinfunction "1_1") (pintype "bidirectional"))
      (node (ref "U3") (pin "23") (pinfunction "SCL/SCLK_23") (pintype "bidirectional"))
      (node (ref "U6") (pin "21") (pinfunction "PA5_21") (pintype "bidirectional"))
    )
    (net (code "20") (name "/NRST") (class "Default")
      (node (ref "C27") (pin "2") (pinfunction "2_2") (pintype "passive"))
      (node (ref "CON8") (pin "2") (pinfunction "2_2") (pintype "passive"))
      (node (ref "R3") (pin "1") (pinfunction "1_1") (pintype "passive"))
      (node (ref "TP36") (pin "1") (pinfunction "1_1") (pintype "bidirectional"))
      (node (ref "U6") (pin "7") (pinfunction "NRST_7") (pintype "bidirectional"))
    )
    (net (code "21") (name "/PA15") (class "Default")
      (node (ref "RA3") (pin "D1") (pinfunction "1_D1") (pintype "passive"))
      (node (ref "U6") (pin "40") (pinfunction "PC9_40") (pintype "bidirectional"))
    )
    (net (code "22") (name "/PB0") (class "Default")
      (node (ref "CON3") (pin "5") (pinfunction "5_5") (pintype "passive"))
      (node (ref "TP20") (pin "1") (pinfunction "1_1") (pintype "bidirectional"))
      (node (ref "U6") (pin "26") (pinfunction "PB0_26") (pintype "bidirectional"))
    )
    (net (code "23") (name "/PB1") (class "Default")
      (node (ref "CON3") (pin "6") (pinfunction "6_6") (pintype "passive"))
      (node (ref "JP1") (pin "1") (pinfunction "1_1") (pintype "passive"))
      (node (ref "TP21") (pin "1") (pinfunction "1_1") (pintype "bidirectional"))
      (node (ref "U6") (pin "27") (pinfunction "PB1_27") (pintype "bidirectional"))
    )
    (net (code "24") (name "/PB3") (class "Default")
      (node (ref "RA3") (pin "C1") (pinfunction "1_C1") (pintype "passive"))
      (node (ref "U6") (pin "41") (pinfunction "PA8_41") (pintype "bidirectional"))
    )
    (net (code "25") (name "/PB4") (class "Default")
      (node (ref "RA3") (pin "B1") (pinfunction "1_B1") (pintype "passive"))
      (node (ref "U6") (pin "50") (pinfunction "PA15_50") (pintype "bidirectional"))
    )
    (net (code "26") (name "/PB5") (class "Default")
      (node (ref "RA3") (pin "A1") (pinfunction "1_A1") (pintype "passive"))
      (node (ref "U6") (pin "55") (pinfunction "PB3_55") (pintype "bidirectional"))
    )
    (net (code "27") (name "/PB6") (class "Default")
      (node (ref "RA2") (pin "D1") (pinfunction "1_D1") (pintype "passive"))
      (node (ref "U6") (pin "56") (pinfunction "PB4_56") (pintype "bidirectional"))
    )
    (net (code "28") (name "/PB7") (class "Default")
      (node (ref "RA2") (pin "C1") (pinfunction "1_C1") (pintype "passive"))
      (node (ref "U6") (pin "57") (pinfunction "PB5_57") (pintype "bidirectional"))
    )
    (net (code "29") (name "/PB8") (class "Default")
      (node (ref "RA2") (pin "B1") (pinfunction "1_B1") (pintype "passive"))
      (node (ref "U6") (pin "58") (pinfunction "PB6_58") (pintype "bidirectional"))
    )
    (net (code "30") (name "/PB9") (class "Default")
      (node (ref "RA2") (pin "A1") (pinfunction "1_A1") (pintype "passive"))
      (node (ref "U6") (pin "59") (pinfunction "PB7_59") (pintype "bidirectional"))
    )
    (net (code "31") (name "/PC6") (class "Default")
      (node (ref "CON3") (pin "4") (pinfunction "4_4") (pintype "passive"))
      (node (ref "TP19") (pin "1") (pinfunction "1_1") (pintype "bidirectional"))
      (node (ref "U6") (pin "37") (pinfunction "PC6_37") (pintype "bidirectional"))
    )
    (net (code "32") (name "/PC7") (class "Default")
      (node (ref "CON3") (pin "3") (pinfunction "3_3") (pintype "passive"))
      (node (ref "TP18") (pin "1") (pinfunction "1_1") (pintype "bidirectional"))
      (node (ref "U6") (pin "38") (pinfunction "PC7_38") (pintype "bidirectional"))
    )
    (net (code "33") (name "/PC8") (class "Default")
      (node (ref "CON3") (pin "2") (pinfunction "2_2") (pintype "passive"))
      (node (ref "TP17") (pin "1") (pinfunction "1_1") (pintype "bidirectional"))
      (node (ref "U6") (pin "39") (pinfunction "PC8_39") (pintype "bidirectional"))
    )
    (net (code "34") (name "/PC13") (class "Default")
      (node (ref "RA4") (pin "C1") (pinfunction "1_C1") (pintype "passive"))
      (node (ref "TP46") (pin "1") (pinfunction "1_1") (pintype "bidirectional"))
      (node (ref "U6") (pin "2") (pinfunction "PC13-RTC_AF1_2") (pintype "bidirectional"))
    )
    (net (code "35") (name "/PC14") (class "Default")
      (node (ref "RA4") (pin "B1") (pinfunction "1_B1") (pintype "passive"))
      (node (ref "TP47") (pin "1") (pinfunction "1_1") (pintype "bidirectional"))
      (node (ref "U6") (pin "3") (pinfunction "PC14-OSC32_IN_3") (pintype "bidirectional"))
    )
    (net (code "36") (name "/PC15") (class "Default")
      (node (ref "RA4") (pin "A1") (pinfunction "1_A1") (pintype "passive"))
      (node (ref "TP48") (pin "1") (pinfunction "1_1") (pintype "bidirectional"))
      (node (ref "U6") (pin "4") (pinfunction "PC15-OSC32_OUT_4") (pintype "bidirectional"))
    )
    (net (code "37") (name "/RC_RX") (class "Default")
      (node (ref "CON7") (pin "4") (pinfunction "4_4") (pintype "passive"))
      (node (ref "TP25") (pin "1") (pinfunction "1_1") (pintype "bidirectional"))
      (node (ref "U7") (pin "2") (pinfunction "I1_2") (pintype "input"))
    )
    (net (code "38") (name "/SCK") (class "Default")
      (node (ref "CON2") (pin "5") (pinfunction "5_5") (pintype "passive"))
      (node (ref "TP15") (pin "1") (pinfunction "1_1") (pintype "bidirectional"))
      (node (ref "U6") (pin "34") (pinfunction "PB13_34") (pintype "bidirectional"))
    )
    (net (code "39") (name "/SCL") (class "Default")
      (node (ref "JP2") (pin "2") (pinfunction "2_2") (pintype "passive"))
      (node (ref "RA1") (pin "A2") (pinfunction "2_A2") (pintype "passive"))
      (node (ref "TP7") (pin "1") (pinfunction "1_1") (pintype "bidirectional"))
      (node (ref "U1") (pin "8") (pinfunction "SCLK_8") (pintype "bidirectional"))
      (node (ref "U2") (pin "4") (pinfunction "SCL/SPC_4") (pintype "bidirectional"))
      (node (ref "U4") (pin "1") (pinfunction "SCL_1") (pintype "bidirectional"))
      (node (ref "U5") (pin "5") (pinfunction "SCL_5") (pintype "input"))
      (node (ref "U6") (pin "29") (pinfunction "PB10_29") (pintype "bidirectional"))
    )
    (net (code "40") (name "/SCL-EXT") (class "Default")
      (node (ref "CON5") (pin "3") (pinfunction "3_3") (pintype "passive"))
      (node (ref "JP2") (pin "1") (pinfunction "1_1") (pintype "passive"))
      (node (ref "RA1") (pin "C1") (pinfunction "1_C1") (pintype "passive"))
      (node (ref "TP22") (pin "1") (pinfunction "1_1") (pintype "bidirectional"))
      (node (ref "U6") (pin "61") (pinfunction "PB8_61") (pintype "bidirectional"))
    )
    (net (code "41") (name "/SDA") (class "Default")
      (node (ref "JP3") (pin "2") (pinfunction "2_2") (pintype "passive"))
      (node (ref "RA1") (pin "B2") (pinfunction "2_B2") (pintype "passive"))
      (node (ref "TP6") (pin "1") (pinfunction "1_1") (pintype "bidirectional"))
      (node (ref "U1") (pin "7") (pinfunction "SDA_7") (pintype "bidirectional"))
      (node (ref "U2") (pin "6") (pinfunction "SDA/SDI/SDO_6") (pintype "bidirectional"))
      (node (ref "U4") (pin "16") (pinfunction "SDA_16") (pintype "bidirectional"))
      (node (ref "U5") (pin "6") (pinfunction "SDA_6") (pintype "bidirectional"))
      (node (ref "U6") (pin "30") (pinfunction "PB11_30") (pintype "bidirectional"))
    )
    (net (code "42") (name "/SDA-EXT") (class "Default")
      (node (ref "CON5") (pin "4") (pinfunction "4_4") (pintype "passive"))
      (node (ref "JP3") (pin "1") (pinfunction "1_1") (pintype "passive"))
      (node (ref "RA1") (pin "D1") (pinfunction "1_D1") (pintype "passive"))
      (node (ref "TP23") (pin "1") (pinfunction "1_1") (pintype "bidirectional"))
      (node (ref "U6") (pin "62") (pinfunction "PB9_62") (pintype "bidirectional"))
    )
    (net (code "43") (name "/SWDCLK") (class "Default")
      (node (ref "CON8") (pin "4") (pinfunction "4_4") (pintype "passive"))
      (node (ref "TP34") (pin "1") (pinfunction "1_1") (pintype "bidirectional"))
      (node (ref "U6") (pin "49") (pinfunction "PA14_49") (pintype "bidirectional"))
    )
    (net (code "44") (name "/SWDIO") (class "Default")
      (node (ref "CON8") (pin "3") (pinfunction "3_3") (pintype "passive"))
      (node (ref "TP35") (pin "1") (pinfunction "1_1") (pintype "bidirectional"))
      (node (ref "U6") (pin "46") (pinfunction "PA13_46") (pintype "bidirectional"))
    )
    (net (code "45") (name "/TELEM_CTS") (class "Default")
      (node (ref "CON1") (pin "6") (pinfunction "6_6") (pintype "passive"))
      (node (ref "TP12") (pin "1") (pinfunction "1_1") (pintype "bidirectional"))
      (node (ref "U6") (pin "14") (pinfunction "PA0-WKUP_14") (pintype "bidirectional"))
    )
    (net (code "46") (name "/TELEM_RTS") (class "Default")
      (node (ref "CON1") (pin "5") (pinfunction "5_5") (pintype "passive"))
      (node (ref "TP11") (pin "1") (pinfunction "1_1") (pintype "bidirectional"))
      (node (ref "U6") (pin "15") (pinfunction "PA1_15") (pintype "bidirectional"))
    )
    (net (code "47") (name "/TELEM_RX") (class "Default")
      (node (ref "CON1") (pin "4") (pinfunction "4_4") (pintype "passive"))
      (node (ref "TP10") (pin "1") (pinfunction "1_1") (pintype "bidirectional"))
      (node (ref "U6") (pin "17") (pinfunction "PA3_17") (pintype "bidirectional"))
    )
    (net (code "48") (name "/TELEM_TX") (class "Default")
      (node (ref "CON1") (pin "3") (pinfunction "3_3") (pintype "passive"))
      (node (ref "TP9") (pin "1") (pinfunction "1_1") (pintype "bidirectional"))
      (node (ref "U6") (pin "16") (pinfunction "PA2_16") (pintype "bidirectional"))
    )
    (net (code "49") (name "/USART5_RX") (class "Default")
      (node (ref "CON4") (pin "4") (pinfunction "4_4") (pintype "passive"))
      (node (ref "TP33") (pin "1") (pinfunction "1_1") (pintype "bidirectional"))
      (node (ref "U6") (pin "54") (pinfunction "PD2_54") (pintype "bidirectional"))
    )
    (net (code "50") (name "/USART5_TX") (class "Default")
      (node (ref "CON4") (pin "3") (pinfunction "3_3") (pintype "passive"))
      (node (ref "TP32") (pin "1") (pinfunction "1_1") (pintype "bidirectional"))
      (node (ref "U6") (pin "53") (pinfunction "PC12_53") (pintype "bidirectional"))
    )
    (net (code "51") (name "3.3V") (class "Default")
      (node (ref "C15") (pin "1") (pinfunction "1_1") (pintype "passive"))
      (node (ref "C17") (pin "1") (pinfunction "1_1") (pintype "passive"))
      (node (ref "C18") (pin "2") (pinfunction "2_2") (pintype "passive"))
      (node (ref "C22") (pin "1") (pinfunction "1_1") (pintype "passive"))
      (node (ref "C26") (pin "1") (pinfunction "1_1") (pintype "passive"))
      (node (ref "C27") (pin "1") (pinfunction "1_1") (pintype "passive"))
      (node (ref "C28") (pin "1") (pinfunction "1_1") (pintype "passive"))
      (node (ref "C29") (pin "2") (pinfunction "2_2") (pintype "passive"))
      (node (ref "C33") (pin "1") (pinfunction "1_1") (pintype "passive"))
      (node (ref "C6") (pin "1") (pinfunction "1_1") (pintype "passive"))
      (node (ref "C9") (pin "2") (pinfunction "2_2") (pintype "passive"))
      (node (ref "CON4") (pin "2") (pinfunction "2_2") (pintype "passive"))
      (node (ref "CON7") (pin "3") (pinfunction "3_3") (pintype "passive"))
      (node (ref "JP4") (pin "1") (pinfunction "1_1") (pintype "passive"))
      (node (ref "R3") (pin "2") (pinfunction "2_2") (pintype "passive"))
      (node (ref "RA1") (pin "A1") (pinfunction "1_A1") (pintype "passive"))
      (node (ref "RA1") (pin "B1") (pinfunction "1_B1") (pintype "passive"))
      (node (ref "RA1") (pin "C2") (pinfunction "2_C2") (pintype "passive"))
      (node (ref "RA1") (pin "D2") (pinfunction "2_D2") (pintype "passive"))
      (node (ref "RA4") (pin "D1") (pinfunction "1_D1") (pintype "passive"))
      (node (ref "TP39") (pin "1") (pinfunction "1_1") (pintype "bidirectional"))
      (node (ref "TP43") (pin "1") (pinfunction "1_1") (pintype "bidirectional"))
      (node (ref "U2") (pin "1") (pinfunction "VDDIO_1") (pintype "bidirectional"))
      (node (ref "U2") (pin "7") (pinfunction "SDO/SA0_7") (pintype "bidirectional"))
      (node (ref "U2") (pin "8") (pinfunction "~{CS}_8") (pintype "bidirectional"))
      (node (ref "U4") (pin "13") (pinfunction "VDDIO_13") (pintype "bidirectional"))
      (node (ref "U4") (pin "4") (pinfunction "S1_4") (pintype "bidirectional"))
      (node (ref "U5") (pin "2") (pinfunction "VDD_2") (pintype "power_in"))
      (node (ref "U6") (pin "1") (pinfunction "VBAT_1") (pintype "power_in"))
      (node (ref "U6") (pin "19") (pinfunction "VDD_19") (pintype "power_in"))
      (node (ref "U6") (pin "32") (pinfunction "VDD_32") (pintype "power_in"))
      (node (ref "U6") (pin "48") (pinfunction "VDD_48") (pintype "power_in"))
      (node (ref "U6") (pin "64") (pinfunction "VDD_64") (pintype "power_in"))
      (node (ref "U7") (pin "5") (pinfunction "VCC_5") (pintype "power_in"))
      (node (ref "U8") (pin "5") (pinfunction "VOUT_5") (pintype "passive"))
    )
    (net (code "52") (name "3.3VA") (class "Default")
      (node (ref "C20") (pin "1") (pinfunction "1_1") (pintype "passive"))
      (node (ref "C39") (pin "1") (pinfunction "1_1") (pintype "passive"))
      (node (ref "FB1") (pin "2") (pinfunction "2_2") (pintype "passive"))
      (node (ref "FB2") (pin "1") (pinfunction "1_1") (pintype "passive"))
      (node (ref "FB4") (pin "1") (pinfunction "1_1") (pintype "passive"))
      (node (ref "FB5") (pin "1") (pinfunction "1_1") (pintype "passive"))
      (node (ref "FB6") (pin "2") (pinfunction "2_2") (pintype "passive"))
      (node (ref "FB7") (pin "2") (pinfunction "2_2") (pintype "passive"))
      (node (ref "TP45") (pin "1") (pinfunction "1_1") (pintype "bidirectional"))
      (node (ref "U10") (pin "5") (pinfunction "VOUT_5") (pintype "passive"))
    )
    (net (code "53") (name "GND") (class "Default")
      (node (ref "C1") (pin "2") (pinfunction "2_2") (pintype "passive"))
      (node (ref "C11") (pin "2") (pinfunction "2_2") (pintype "passive"))
      (node (ref "C12") (pin "2") (pinfunction "2_2") (pintype "passive"))
      (node (ref "C13") (pin "2") (pinfunction "2_2") (pintype "passive"))
      (node (ref "C14") (pin "2") (pinfunction "2_2") (pintype "passive"))
      (node (ref "C15") (pin "2") (pinfunction "2_2") (pintype "passive"))
      (node (ref "C16") (pin "1") (pinfunction "1_1") (pintype "passive"))
      (node (ref "C17") (pin "2") (pinfunction "2_2") (pintype "passive"))
      (node (ref "C18") (pin "1") (pinfunction "1_1") (pintype "passive"))
      (node (ref "C19") (pin "2") (pinfunction "2_2") (pintype "passive"))
      (node (ref "C2") (pin "2") (pinfunction "2_2") (pintype "passive"))
      (node (ref "C20") (pin "2") (pinfunction "2_2") (pintype "passive"))
      (node (ref "C21") (pin "2") (pinfunction "2_2") (pintype "passive"))
      (node (ref "C22") (pin "2") (pinfunction "2_2") (pintype "passive"))
      (node (ref "C23") (pin "2") (pinfunction "2_2") (pintype "passive"))
      (node (ref "C24") (pin "2") (pinfunction "2_2") (pintype "passive"))
      (node (ref "C25") (pin "2") (pinfunction "2_2") (pintype "passive"))
      (node (ref "C26") (pin "2") (pinfunction "2_2") (pintype "passive"))
      (node (ref "C28") (pin "2") (pinfunction "2_2") (pintype "passive"))
      (node (ref "C29") (pin "1") (pinfunction "1_1") (pintype "passive"))
      (node (ref "C3") (pin "2") (pinfunction "2_2") (pintype "passive"))
      (node (ref "C30") (pin "2") (pinfunction "2_2") (pintype "passive"))
      (node (ref "C31") (pin "2") (pinfunction "2_2") (pintype "passive"))
      (node (ref "C32") (pin "2") (pinfunction "2_2") (pintype "passive"))
      (node (ref "C33") (pin "2") (pinfunction "2_2") (pintype "passive"))
      (node (ref "C34") (pin "2") (pinfunction "2_2") (pintype "passive"))
      (node (ref "C35") (pin "2") (pinfunction "2_2") (pintype "passive"))
      (node (ref "C36") (pin "2") (pinfunction "2_2") (pintype "passive"))
      (node (ref "C37") (pin "2") (pinfunction "2_2") (pintype "passive"))
      (node (ref "C38") (pin "2") (pinfunction "2_2") (pintype "passive"))
      (node (ref "C39") (pin "2") (pinfunction "2_2") (pintype "passive"))
      (node (ref "C4") (pin "2") (pinfunction "2_2") (pintype "passive"))
      (node (ref "C5") (pin "2") (pinfunction "2_2") (pintype "passive"))
      (node (ref "C6") (pin "2") (pinfunction "2_2") (pintype "passive"))
      (node (ref "C7") (pin "2") (pinfunction "2_2") (pintype "passive"))
      (node (ref "C8") (pin "2") (pinfunction "2_2") (pintype "passive"))
      (node (ref "C9") (pin "1") (pinfunction "1_1") (pintype "passive"))
      (node (ref "CON1") (pin "1") (pinfunction "1_1") (pintype "passive"))
      (node (ref "CON2") (pin "1") (pinfunction "1_1") (pintype "passive"))
      (node (ref "CON3") (pin "1") (pinfunction "1_1") (pintype "passive"))
      (node (ref "CON4") (pin "1") (pinfunction "1_1") (pintype "passive"))
      (node (ref "CON5") (pin "1") (pinfunction "1_1") (pintype "passive"))
      (node (ref "CON6") (pin "1") (pinfunction "1_1") (pintype "passive"))
      (node (ref "CON7") (pin "1") (pinfunction "1_1") (pintype "passive"))
      (node (ref "CON8") (pin "1") (pinfunction "1_1") (pintype "passive"))
      (node (ref "CON9") (pin "4") (pinfunction "4_4") (pintype "passive"))
      (node (ref "J1") (pin "3") (pinfunction "3_3") (pintype "passive"))
      (node (ref "J2") (pin "3") (pinfunction "3_3") (pintype "passive"))
      (node (ref "J3") (pin "3") (pinfunction "3_3") (pintype "passive"))
      (node (ref "J4") (pin "3") (pinfunction "3_3") (pintype "passive"))
      (node (ref "J5") (pin "3") (pinfunction "3_3") (pintype "passive"))
      (node (ref "J6") (pin "3") (pinfunction "3_3") (pintype "passive"))
      (node (ref "J7") (pin "3") (pinfunction "3_3") (pintype "passive"))
      (node (ref "J8") (pin "3") (pinfunction "3_3") (pintype "passive"))
      (node (ref "LED1") (pin "2") (pinfunction "C_2") (pintype "passive"))
      (node (ref "LED2") (pin "2") (pinfunction "C_2") (pintype "passive"))
      (node (ref "LED3") (pin "2") (pinfunction "C_2") (pintype "passive"))
      (node (ref "LED4") (pin "2") (pinfunction "C_2") (pintype "passive"))
      (node (ref "Q1") (pin "2") (pinfunction "GND_2") (pintype "power_in"))
      (node (ref "Q1") (pin "4") (pinfunction "GND_4") (pintype "power_in"))
      (node (ref "R4") (pin "2") (pinfunction "2_2") (pintype "passive"))
      (node (ref "U1") (pin "3") (pinfunction "GND_3") (pintype "power_in"))
      (node (ref "U1") (pin "4") (pinfunction "CSB_4") (pintype "bidirectional"))
      (node (ref "U10") (pin "2") (pinfunction "GND_2") (pintype "power_in"))
      (node (ref "U2") (pin "10") (pinfunction "GND_10") (pintype "bidirectional"))
      (node (ref "U2") (pin "12") (pinfunction "GND_12") (pintype "bidirectional"))
      (node (ref "U2") (pin "13") (pinfunction "GND_13") (pintype "bidirectional"))
      (node (ref "U2") (pin "16") (pinfunction "GND_16") (pintype "bidirectional"))
      (node (ref "U2") (pin "5") (pinfunction "GND_5") (pintype "bidirectional"))
      (node (ref "U3") (pin "1") (pinfunction "CLKIN_1") (pintype "bidirectional"))
      (node (ref "U3") (pin "11") (pinfunction "FSYNC_11") (pintype "bidirectional"))
      (node (ref "U3") (pin "18") (pinfunction "GND_18") (pintype "bidirectional"))
      (node (ref "U4") (pin "11") (pinfunction "GND_11") (pintype "bidirectional"))
      (node (ref "U4") (pin "9") (pinfunction "GND_9") (pintype "bidirectional"))
      (node (ref "U5") (pin "7") (pinfunction "GND_7") (pintype "power_in"))
      (node (ref "U6") (pin "12") (pinfunction "VSSA_12") (pintype "bidirectional"))
      (node (ref "U6") (pin "18") (pinfunction "VSS_18") (pintype "power_in"))
      (node (ref "U6") (pin "63") (pinfunction "VSS_63") (pintype "power_in"))
      (node (ref "U7") (pin "3") (pinfunction "GND_3") (pintype "power_in"))
      (node (ref "U8") (pin "2") (pinfunction "GND_2") (pintype "power_in"))
      (node (ref "U9") (pin "2") (pinfunction "GND_2") (pintype "power_in"))
      (node (ref "USB1") (pin "GND") (pinfunction "GND_GND") (pintype "bidirectional"))
    )
    (net (code "54") (name "Net-(C2-Pad1)") (class "Default")
      (node (ref "C2") (pin "1") (pinfunction "1_1") (pintype "passive"))
      (node (ref "C3") (pin "1") (pinfunction "1_1") (pintype "passive"))
      (node (ref "FB1") (pin "1") (pinfunction "1_1") (pintype "passive"))
      (node (ref "U2") (pin "14") (pinfunction "VDD_14") (pintype "bidirectional"))
      (node (ref "U2") (pin "15") (pinfunction "VDD_15") (pintype "bidirectional"))
    )
    (net (code "55") (name "Net-(C16-Pad2)") (class "Default")
      (node (ref "C16") (pin "2") (pinfunction "2_2") (pintype "passive"))
      (node (ref "U6") (pin "31") (pinfunction "VCAP_31") (pintype "power_in"))
    )
    (net (code "56") (name "Net-(C21-Pad1)") (class "Default")
      (node (ref "C21") (pin "1") (pinfunction "1_1") (pintype "passive"))
      (node (ref "CON6") (pin "2") (pinfunction "2_2") (pintype "passive"))
      (node (ref "JP4") (pin "2") (pinfunction "2_2") (pintype "passive"))
    )
    (net (code "57") (name "Net-(C25-Pad1)") (class "Default")
      (node (ref "C25") (pin "1") (pinfunction "1_1") (pintype "passive"))
      (node (ref "U6") (pin "47") (pinfunction "VCAP_47") (pintype "power_in"))
    )
    (net (code "58") (name "Net-(D1-P$1)") (class "Default")
      (node (ref "C30") (pin "1") (pinfunction "1_1") (pintype "passive"))
      (node (ref "D1") (pin "1") (pinfunction "P$1_1") (pintype "input"))
      (node (ref "F1") (pin "2") (pinfunction "2_2") (pintype "bidirectional"))
    )
    (net (code "59") (name "Net-(FB6-Pad1)") (class "Default")
      (node (ref "FB6") (pin "1") (pinfunction "1_1") (pintype "passive"))
      (node (ref "JP4") (pin "3") (pinfunction "3_3") (pintype "passive"))
    )
    (net (code "60") (name "Net-(LED1-A)") (class "Default")
      (node (ref "LED1") (pin "1") (pinfunction "A_1") (pintype "passive"))
      (node (ref "RA4") (pin "A2") (pinfunction "2_A2") (pintype "passive"))
    )
    (net (code "61") (name "Net-(LED2-A)") (class "Default")
      (node (ref "LED2") (pin "1") (pinfunction "A_1") (pintype "passive"))
      (node (ref "RA4") (pin "B2") (pinfunction "2_B2") (pintype "passive"))
    )
    (net (code "62") (name "Net-(LED3-A)") (class "Default")
      (node (ref "LED3") (pin "1") (pinfunction "A_1") (pintype "passive"))
      (node (ref "RA4") (pin "C2") (pinfunction "2_C2") (pintype "passive"))
    )
    (net (code "63") (name "Net-(LED4-A)") (class "Default")
      (node (ref "LED4") (pin "1") (pinfunction "A_1") (pintype "passive"))
      (node (ref "RA4") (pin "D2") (pinfunction "2_D2") (pintype "passive"))
    )
    (net (code "64") (name "Net-(Q1-2)") (class "Default")
      (node (ref "C23") (pin "1") (pinfunction "1_1") (pintype "passive"))
      (node (ref "Q1") (pin "3") (pinfunction "2_3") (pintype "passive"))
      (node (ref "U6") (pin "6") (pinfunction "PH1-OSC_OUT_6") (pintype "bidirectional"))
    )
    (net (code "65") (name "Net-(R1-Pad1)") (class "Default")
      (node (ref "R1") (pin "1") (pinfunction "1_1") (pintype "passive"))
      (node (ref "USB1") (pin "D+") (pinfunction "D+_D+") (pintype "bidirectional"))
    )
    (net (code "66") (name "Net-(R2-Pad1)") (class "Default")
      (node (ref "R2") (pin "1") (pinfunction "1_1") (pintype "passive"))
      (node (ref "USB1") (pin "D-") (pinfunction "D-_D-") (pintype "bidirectional"))
    )
    (net (code "67") (name "Net-(RA2A-2)") (class "Default")
      (node (ref "J1") (pin "1") (pinfunction "1_1") (pintype "passive"))
      (node (ref "RA2") (pin "A2") (pinfunction "2_A2") (pintype "passive"))
    )
    (net (code "68") (name "Net-(RA2B-2)") (class "Default")
      (node (ref "J2") (pin "1") (pinfunction "1_1") (pintype "passive"))
      (node (ref "RA2") (pin "B2") (pinfunction "2_B2") (pintype "passive"))
    )
    (net (code "69") (name "Net-(RA2C-2)") (class "Default")
      (node (ref "J3") (pin "1") (pinfunction "1_1") (pintype "passive"))
      (node (ref "RA2") (pin "C2") (pinfunction "2_C2") (pintype "passive"))
    )
    (net (code "70") (name "Net-(RA2D-2)") (class "Default")
      (node (ref "J4") (pin "1") (pinfunction "1_1") (pintype "passive"))
      (node (ref "RA2") (pin "D2") (pinfunction "2_D2") (pintype "passive"))
    )
    (net (code "71") (name "Net-(RA3A-2)") (class "Default")
      (node (ref "J5") (pin "1") (pinfunction "1_1") (pintype "passive"))
      (node (ref "RA3") (pin "A2") (pinfunction "2_A2") (pintype "passive"))
    )
    (net (code "72") (name "Net-(RA3B-2)") (class "Default")
      (node (ref "J6") (pin "1") (pinfunction "1_1") (pintype "passive"))
      (node (ref "RA3") (pin "B2") (pinfunction "2_B2") (pintype "passive"))
    )
    (net (code "73") (name "Net-(RA3C-2)") (class "Default")
      (node (ref "J7") (pin "1") (pinfunction "1_1") (pintype "passive"))
      (node (ref "RA3") (pin "C2") (pinfunction "2_C2") (pintype "passive"))
    )
    (net (code "74") (name "Net-(RA3D-2)") (class "Default")
      (node (ref "J8") (pin "1") (pinfunction "1_1") (pintype "passive"))
      (node (ref "RA3") (pin "D2") (pinfunction "2_D2") (pintype "passive"))
    )
    (net (code "75") (name "Net-(U1-PS)") (class "Default")
      (node (ref "C1") (pin "1") (pinfunction "1_1") (pintype "passive"))
      (node (ref "FB2") (pin "2") (pinfunction "2_2") (pintype "passive"))
      (node (ref "U1") (pin "1") (pinfunction "VDD_1") (pintype "power_in"))
      (node (ref "U1") (pin "2") (pinfunction "PS_2") (pintype "bidirectional"))
    )
    (net (code "76") (name "Net-(U2-INT1)") (class "Default")
      (node (ref "JP1") (pin "2") (pinfunction "2_2") (pintype "passive"))
      (node (ref "U2") (pin "9") (pinfunction "INT1_9") (pintype "bidirectional"))
    )
    (net (code "77") (name "Net-(U3-CPOUT)") (class "Default")
      (node (ref "C11") (pin "1") (pinfunction "1_1") (pintype "passive"))
      (node (ref "U3") (pin "20") (pinfunction "CPOUT_20") (pintype "bidirectional"))
    )
    (net (code "78") (name "Net-(U3-REGOUT)") (class "Default")
      (node (ref "C12") (pin "1") (pinfunction "1_1") (pintype "passive"))
      (node (ref "U3") (pin "10") (pinfunction "REGOUT_10") (pintype "bidirectional"))
    )
    (net (code "79") (name "Net-(U3-VDD)") (class "Default")
      (node (ref "C13") (pin "1") (pinfunction "1_1") (pintype "passive"))
      (node (ref "C14") (pin "1") (pinfunction "1_1") (pintype "passive"))
      (node (ref "FB5") (pin "2") (pinfunction "2_2") (pintype "passive"))
      (node (ref "U3") (pin "13") (pinfunction "VDD_13") (pintype "bidirectional"))
    )
    (net (code "80") (name "Net-(U4-C1)") (class "Default")
      (node (ref "C8") (pin "1") (pinfunction "1_1") (pintype "passive"))
      (node (ref "U4") (pin "10") (pinfunction "C1_10") (pintype "bidirectional"))
    )
    (net (code "81") (name "Net-(U4-SETC)") (class "Default")
      (node (ref "C10") (pin "2") (pinfunction "2_2") (pintype "passive"))
      (node (ref "U4") (pin "12") (pinfunction "SETC_12") (pintype "bidirectional"))
    )
    (net (code "82") (name "Net-(U4-SETP)") (class "Default")
      (node (ref "C10") (pin "1") (pinfunction "1_1") (pintype "passive"))
      (node (ref "U4") (pin "8") (pinfunction "SETP_8") (pintype "bidirectional"))
    )
    (net (code "83") (name "Net-(U4-VDD)") (class "Default")
      (node (ref "C4") (pin "1") (pinfunction "1_1") (pintype "passive"))
      (node (ref "C5") (pin "1") (pinfunction "1_1") (pintype "passive"))
      (node (ref "FB3") (pin "1") (pinfunction "1_1") (pintype "passive"))
      (node (ref "U4") (pin "2") (pinfunction "VDD_2") (pintype "bidirectional"))
    )
    (net (code "84") (name "Net-(U5-VDDIO)") (class "Default")
      (node (ref "C7") (pin "1") (pinfunction "1_1") (pintype "passive"))
      (node (ref "FB4") (pin "2") (pinfunction "2_2") (pintype "passive"))
      (node (ref "U5") (pin "3") (pinfunction "VDDIO_3") (pintype "power_in"))
    )
    (net (code "85") (name "Net-(U6-BOOT0)") (class "Default")
      (node (ref "R4") (pin "1") (pinfunction "1_1") (pintype "passive"))
      (node (ref "TP37") (pin "1") (pinfunction "1_1") (pintype "bidirectional"))
      (node (ref "TP38") (pin "1") (pinfunction "1_1") (pintype "bidirectional"))
      (node (ref "U6") (pin "60") (pinfunction "BOOT0_60") (pintype "bidirectional"))
    )
    (net (code "86") (name "Net-(U6-PA9)") (class "Default")
      (node (ref "F1") (pin "1") (pinfunction "1_1") (pintype "bidirectional"))
      (node (ref "TP31") (pin "1") (pinfunction "1_1") (pintype "bidirectional"))
      (node (ref "U6") (pin "42") (pinfunction "PA9_42") (pintype "bidirectional"))
      (node (ref "USB1") (pin "VBUS") (pinfunction "VBUS_VBUS") (pintype "bidirectional"))
    )
    (net (code "87") (name "Net-(U6-PA10)") (class "Default")
      (node (ref "TP26") (pin "1") (pinfunction "1_1") (pintype "bidirectional"))
      (node (ref "U6") (pin "43") (pinfunction "PA10_43") (pintype "bidirectional"))
      (node (ref "U7") (pin "4") (pinfunction "O_4") (pintype "output"))
    )
    (net (code "88") (name "Net-(U6-PA11)") (class "Default")
      (node (ref "R2") (pin "2") (pinfunction "2_2") (pintype "passive"))
      (node (ref "U6") (pin "44") (pinfunction "PA11_44") (pintype "bidirectional"))
    )
    (net (code "89") (name "Net-(U6-PA12)") (class "Default")
      (node (ref "R1") (pin "2") (pinfunction "2_2") (pintype "passive"))
      (node (ref "U6") (pin "45") (pinfunction "PA12_45") (pintype "bidirectional"))
    )
    (net (code "90") (name "Net-(U6-PC5)") (class "Default")
      (node (ref "TP24") (pin "1") (pinfunction "1_1") (pintype "bidirectional"))
      (node (ref "U6") (pin "25") (pinfunction "PC5_25") (pintype "bidirectional"))
      (node (ref "U7") (pin "1") (pinfunction "I0_1") (pintype "input"))
    )
    (net (code "91") (name "Net-(U6-PH0-OSC_IN)") (class "Default")
      (node (ref "C24") (pin "1") (pinfunction "1_1") (pintype "passive"))
      (node (ref "Q1") (pin "1") (pinfunction "1_1") (pintype "passive"))
      (node (ref "U6") (pin "5") (pinfunction "PH0-OSC_IN_5") (pintype "bidirectional"))
    )
    (net (code "92") (name "Net-(U6-VDDA)") (class "Default")
      (node (ref "C19") (pin "1") (pinfunction "1_1") (pintype "passive"))
      (node (ref "FB7") (pin "1") (pinfunction "1_1") (pintype "passive"))
      (node (ref "U6") (pin "13") (pinfunction "VDDA_13") (pintype "bidirectional"))
    )
    (net (code "93") (name "Net-(U8-BYPASS)") (class "Default")
      (node (ref "C32") (pin "1") (pinfunction "1_1") (pintype "passive"))
      (node (ref "U8") (pin "4") (pinfunction "BYPASS_4") (pintype "input"))
    )
    (net (code "94") (name "Net-(U9-BYPASS)") (class "Default")
      (node (ref "C35") (pin "1") (pinfunction "1_1") (pintype "passive"))
      (node (ref "U9") (pin "4") (pinfunction "BYPASS_4") (pintype "input"))
    )
    (net (code "95") (name "Net-(U10-BYPASS)") (class "Default")
      (node (ref "C38") (pin "1") (pinfunction "1_1") (pintype "passive"))
      (node (ref "U10") (pin "4") (pinfunction "BYPASS_4") (pintype "input"))
    )
    (net (code "96") (name "VCC") (class "Default")
      (node (ref "C31") (pin "1") (pinfunction "1_1") (pintype "passive"))
      (node (ref "C34") (pin "1") (pinfunction "1_1") (pintype "passive"))
      (node (ref "C37") (pin "1") (pinfunction "1_1") (pintype "passive"))
      (node (ref "CON1") (pin "2") (pinfunction "2_2") (pintype "passive"))
      (node (ref "CON2") (pin "2") (pinfunction "2_2") (pintype "passive"))
      (node (ref "CON5") (pin "2") (pinfunction "2_2") (pintype "passive"))
      (node (ref "CON7") (pin "2") (pinfunction "2_2") (pintype "passive"))
      (node (ref "CON9") (pin "3") (pinfunction "3_3") (pintype "passive"))
      (node (ref "D1") (pin "3") (pinfunction "P$3_3") (pintype "output"))
      (node (ref "F2") (pin "2") (pinfunction "2_2") (pintype "bidirectional"))
      (node (ref "U10") (pin "1") (pinfunction "VIN_1") (pintype "power_in"))
      (node (ref "U10") (pin "3") (pinfunction "ON_OFF_3") (pintype "input"))
      (node (ref "U8") (pin "1") (pinfunction "VIN_1") (pintype "power_in"))
      (node (ref "U8") (pin "3") (pinfunction "ON_OFF_3") (pintype "input"))
      (node (ref "U9") (pin "1") (pinfunction "VIN_1") (pintype "power_in"))
      (node (ref "U9") (pin "3") (pinfunction "ON_OFF_3") (pintype "input"))
    )
    (net (code "97") (name "unconnected-(D1-P$2-Pad2)") (class "Default")
      (node (ref "D1") (pin "2") (pinfunction "P$2_2") (pintype "input"))
    )
    (net (code "98") (name "unconnected-(U2-INT2-Pad11)") (class "Default")
      (node (ref "U2") (pin "11") (pinfunction "INT2_11") (pintype "bidirectional"))
    )
    (net (code "99") (name "unconnected-(U3-AUX_CL-Pad7)") (class "Default")
      (node (ref "U3") (pin "7") (pinfunction "AUX_CL_7") (pintype "bidirectional"))
    )
    (net (code "100") (name "unconnected-(U3-AUX_DA-Pad6)") (class "Default")
      (node (ref "U3") (pin "6") (pinfunction "AUX_DA_6") (pintype "bidirectional"))
    )
    (net (code "101") (name "unconnected-(U3-CLKOUT-Pad22)") (class "Default")
      (node (ref "U3") (pin "22") (pinfunction "CLKOUT_22") (pintype "bidirectional"))
    )
    (net (code "102") (name "unconnected-(U4-NC-Pad3)") (class "Default")
      (node (ref "U4") (pin "3") (pinfunction "NC_3") (pintype "bidirectional"))
    )
    (net (code "103") (name "unconnected-(U4-NC-Pad5)") (class "Default")
      (node (ref "U4") (pin "5") (pinfunction "NC_5") (pintype "bidirectional"))
    )
    (net (code "104") (name "unconnected-(U4-NC-Pad6)") (class "Default")
      (node (ref "U4") (pin "6") (pinfunction "NC_6") (pintype "bidirectional"))
    )
    (net (code "105") (name "unconnected-(U4-NC-Pad7)") (class "Default")
      (node (ref "U4") (pin "7") (pinfunction "NC_7") (pintype "bidirectional"))
    )
    (net (code "106") (name "unconnected-(U4-NC-Pad14)") (class "Default")
      (node (ref "U4") (pin "14") (pinfunction "NC_14") (pintype "bidirectional"))
    )
  )
)
